# DispenGSM.net
KiCad netlist of a schematic drawn in EAGLE
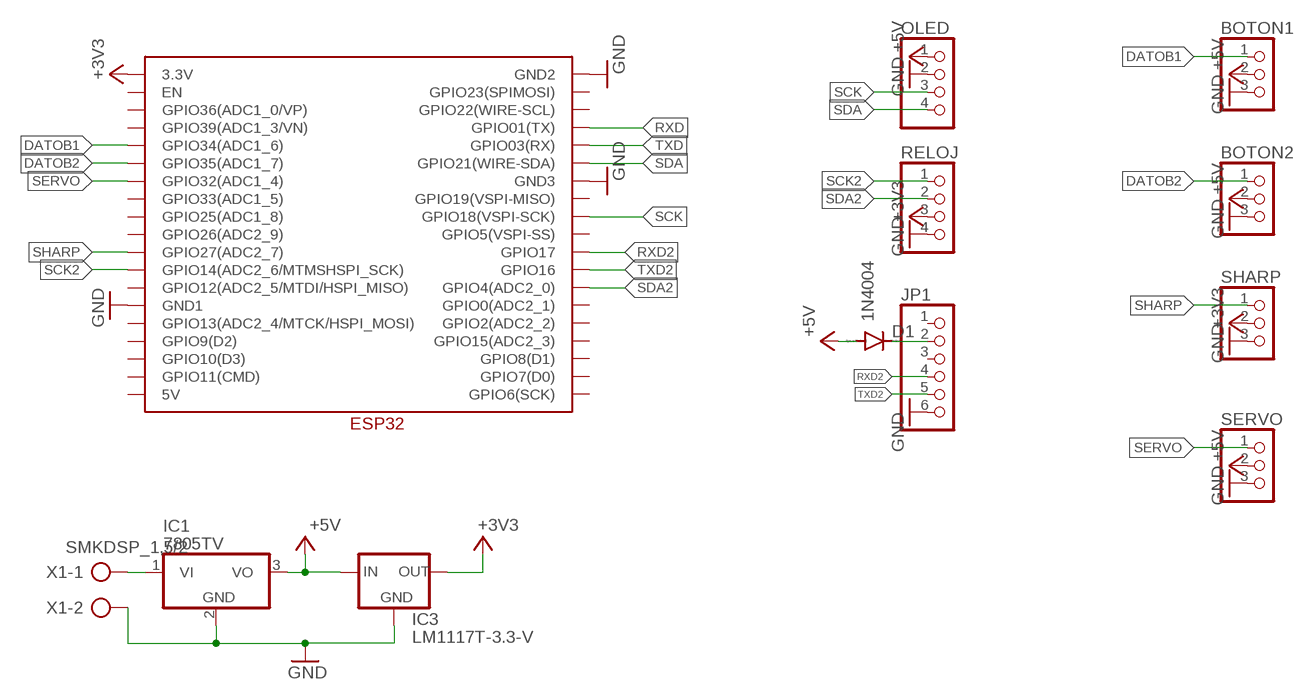
[diagram p0: schematic, sheet 1]

(export (version "E")
  (design (tool "Eeschema 10.0.6"))
  (components
    (comp (ref "BOTON1")
      (value "PINHD-1X3")
      (footprint "eagle-import:1X03")
      (libsource (lib "eagle-import") (part "PINHD-1X3"))
    )
    (comp (ref "BOTON2")
      (value "PINHD-1X3")
      (footprint "eagle-import:1X03")
      (libsource (lib "eagle-import") (part "PINHD-1X3"))
    )
    (comp (ref "D1")
      (value "1N4004")
      (footprint "eagle-import:DO41-10")
      (libsource (lib "eagle-import") (part "1N4004"))
    )
    (comp (ref "IC1")
      (value "7805TV")
      (footprint "eagle-import:TO220V")
      (libsource (lib "eagle-import") (part "78TV05"))
    )
    (comp (ref "IC3")
      (value "LM1117T-3.3-V")
      (footprint "eagle-import:TO220V")
      (libsource (lib "eagle-import") (part "LM1117T--V3.3"))
    )
    (comp (ref "JP1")
      (value "PINHD-1X6")
      (footprint "eagle-import:1X06")
      (libsource (lib "eagle-import") (part "PINHD-1X6"))
    )
    (comp (ref "OLED")
      (value "PINHD-1X4")
      (footprint "eagle-import:1X04")
      (libsource (lib "eagle-import") (part "PINHD-1X4"))
    )
    (comp (ref "RELOJ")
      (value "PINHD-1X4")
      (footprint "eagle-import:1X04")
      (libsource (lib "eagle-import") (part "PINHD-1X4"))
    )
    (comp (ref "SERVO")
      (value "PINHD-1X3")
      (footprint "eagle-import:1X03")
      (libsource (lib "eagle-import") (part "PINHD-1X3"))
    )
    (comp (ref "SHARP")
      (value "PINHD-1X3")
      (footprint "eagle-import:1X03")
      (libsource (lib "eagle-import") (part "PINHD-1X3"))
    )
    (comp (ref "U$1")
      (value "ESP32WESP32W")
      (footprint "eagle-import:ESP32W")
      (libsource (lib "eagle-import") (part "ESP32WESP32W"))
    )
    (comp (ref "X1")
      (value "SMKDSP_1,5/2")
      (footprint "eagle-import:SMKDSP_1,5_2")
      (fields (field (name "MF") "FARNELL") (field (name "MPN") "1733570"))
      (libsource (lib "eagle-import") (part "SMKDSP_1,5/2"))
    )
  )
  (nets
    (net (code "1") (name "+3V3") (class "Default")
      (node (ref "IC3") (pin "2") (pinfunction "OUT_2") (pintype "passive"))
      (node (ref "RELOJ") (pin "3") (pinfunction "3_3") (pintype "passive"))
      (node (ref "SHARP") (pin "2") (pinfunction "2_2") (pintype "passive"))
      (node (ref "U$1") (pin "3.3V") (pinfunction "3.3V_3.3V") (pintype "bidirectional"))
    )
    (net (code "2") (name "+5V") (class "Default")
      (node (ref "BOTON1") (pin "2") (pinfunction "2_2") (pintype "passive"))
      (node (ref "BOTON2") (pin "2") (pinfunction "2_2") (pintype "passive"))
      (node (ref "D1") (pin "A") (pinfunction "A_A") (pintype "passive"))
      (node (ref "IC1") (pin "3") (pinfunction "VO_3") (pintype "passive"))
      (node (ref "IC3") (pin "3") (pinfunction "IN_3") (pintype "input"))
      (node (ref "OLED") (pin "1") (pinfunction "1_1") (pintype "passive"))
      (node (ref "SERVO") (pin "2") (pinfunction "2_2") (pintype "passive"))
    )
    (net (code "3") (name "DATOB1") (class "Default")
      (node (ref "BOTON1") (pin "1") (pinfunction "1_1") (pintype "passive"))
      (node (ref "U$1") (pin "GPIO34") (pinfunction "GPIO34(ADC1_6)_GPIO34") (pintype "bidirectional"))
    )
    (net (code "4") (name "DATOB2") (class "Default")
      (node (ref "BOTON2") (pin "1") (pinfunction "1_1") (pintype "passive"))
      (node (ref "U$1") (pin "GPIO35") (pinfunction "GPIO35(ADC1_7)_GPIO35") (pintype "bidirectional"))
    )
    (net (code "5") (name "GND") (class "Default")
      (node (ref "BOTON1") (pin "3") (pinfunction "3_3") (pintype "passive"))
      (node (ref "BOTON2") (pin "3") (pinfunction "3_3") (pintype "passive"))
      (node (ref "IC1") (pin "2") (pinfunction "GND_2") (pintype "passive"))
      (node (ref "IC3") (pin "1") (pinfunction "GND_1") (pintype "input"))
      (node (ref "JP1") (pin "6") (pinfunction "6_6") (pintype "passive"))
      (node (ref "OLED") (pin "2") (pinfunction "2_2") (pintype "passive"))
      (node (ref "RELOJ") (pin "4") (pinfunction "4_4") (pintype "passive"))
      (node (ref "SERVO") (pin "3") (pinfunction "3_3") (pintype "passive"))
      (node (ref "SHARP") (pin "3") (pinfunction "3_3") (pintype "passive"))
      (node (ref "U$1") (pin "GND1") (pinfunction "GND1_GND1") (pintype "bidirectional"))
      (node (ref "U$1") (pin "GND2") (pinfunction "GND2_GND2") (pintype "bidirectional"))
      (node (ref "U$1") (pin "GND3") (pinfunction "GND3_GND3") (pintype "bidirectional"))
      (node (ref "X1") (pin "2") (pinfunction "KL_2") (pintype "passive"))
    )
    (net (code "6") (name "Net-(D1-PadC)") (class "Default")
      (node (ref "D1") (pin "C") (pinfunction "C_C") (pintype "passive"))
      (node (ref "JP1") (pin "2") (pinfunction "2_2") (pintype "passive"))
    )
    (net (code "7") (name "Net-(IC1-VI)") (class "Default")
      (node (ref "IC1") (pin "1") (pinfunction "VI_1") (pintype "input"))
      (node (ref "X1") (pin "1") (pinfunction "KL_1") (pintype "passive"))
    )
    (net (code "8") (name "RXD") (class "Default")
      (node (ref "U$1") (pin "TX") (pinfunction "GPIO01(TX)_TX") (pintype "bidirectional"))
    )
    (net (code "9") (name "RXD2") (class "Default")
      (node (ref "JP1") (pin "4") (pinfunction "4_4") (pintype "passive"))
      (node (ref "U$1") (pin "GPIO17") (pinfunction "GPIO17_GPIO17") (pintype "bidirectional"))
    )
    (net (code "10") (name "SCK") (class "Default")
      (node (ref "OLED") (pin "3") (pinfunction "3_3") (pintype "passive"))
      (node (ref "U$1") (pin "GPIO18") (pinfunction "GPIO18(VSPI-SCK)_GPIO18") (pintype "bidirectional"))
    )
    (net (code "11") (name "SCK2") (class "Default")
      (node (ref "RELOJ") (pin "1") (pinfunction "1_1") (pintype "passive"))
      (node (ref "U$1") (pin "GPIO14") (pinfunction "GPIO14(ADC2_6/MTMSHSPI_SCK)_GPIO14") (pintype "bidirectional"))
    )
    (net (code "12") (name "SDA") (class "Default")
      (node (ref "OLED") (pin "4") (pinfunction "4_4") (pintype "passive"))
      (node (ref "U$1") (pin "GPIO21") (pinfunction "GPIO21(WIRE-SDA)_GPIO21") (pintype "bidirectional"))
    )
    (net (code "13") (name "SDA2") (class "Default")
      (node (ref "RELOJ") (pin "2") (pinfunction "2_2") (pintype "passive"))
      (node (ref "U$1") (pin "GPIO4") (pinfunction "GPIO4(ADC2_0)_GPIO4") (pintype "bidirectional"))
    )
    (net (code "14") (name "SERVO") (class "Default")
      (node (ref "SERVO") (pin "1") (pinfunction "1_1") (pintype "passive"))
      (node (ref "U$1") (pin "GPIO32") (pinfunction "GPIO32(ADC1_4)_GPIO32") (pintype "bidirectional"))
    )
    (net (code "15") (name "SHARP") (class "Default")
      (node (ref "SHARP") (pin "1") (pinfunction "1_1") (pintype "passive"))
      (node (ref "U$1") (pin "GPIO27") (pinfunction "GPIO27(ADC2_7)_GPIO27") (pintype "bidirectional"))
    )
    (net (code "16") (name "TXD") (class "Default")
      (node (ref "U$1") (pin "RX") (pinfunction "GPIO03(RX)_RX") (pintype "bidirectional"))
    )
    (net (code "17") (name "TXD2") (class "Default")
      (node (ref "JP1") (pin "5") (pinfunction "5_5") (pintype "passive"))
      (node (ref "U$1") (pin "GPIO16") (pinfunction "GPIO16_GPIO16") (pintype "bidirectional"))
    )
    (net (code "18") (name "unconnected-(JP1-Pad1)") (class "Default")
      (node (ref "JP1") (pin "1") (pinfunction "1_1") (pintype "passive"))
    )
    (net (code "19") (name "unconnected-(JP1-Pad3)") (class "Default")
      (node (ref "JP1") (pin "3") (pinfunction "3_3") (pintype "passive"))
    )
    (net (code "20") (name "unconnected-(U$1-GPIO0(ADC2_1)-PadGPIO0)") (class "Default")
      (node (ref "U$1") (pin "GPIO0") (pinfunction "GPIO0(ADC2_1)_GPIO0") (pintype "bidirectional"))
    )
    (net (code "21") (name "unconnected-(U$1-GPIO2(ADC2_2)-PadGPIO2)") (class "Default")
      (node (ref "U$1") (pin "GPIO2") (pinfunction "GPIO2(ADC2_2)_GPIO2") (pintype "bidirectional"))
    )
    (net (code "22") (name "unconnected-(U$1-GPIO5(VSPI-SS)-PadGPIO5)") (class "Default")
      (node (ref "U$1") (pin "GPIO5") (pinfunction "GPIO5(VSPI-SS)_GPIO5") (pintype "bidirectional"))
    )
    (net (code "23") (name "unconnected-(U$1-GPIO6(SCK)-PadCLK)") (class "Default")
      (node (ref "U$1") (pin "CLK") (pinfunction "GPIO6(SCK)_CLK") (pintype "bidirectional"))
    )
    (net (code "24") (name "unconnected-(U$1-GPIO7(D0)-PadSDO)") (class "Default")
      (node (ref "U$1") (pin "SDO") (pinfunction "GPIO7(D0)_SDO") (pintype "bidirectional"))
    )
    (net (code "25") (name "unconnected-(U$1-GPIO8(D1)-PadSDI)") (class "Default")
      (node (ref "U$1") (pin "SDI") (pinfunction "GPIO8(D1)_SDI") (pintype "bidirectional"))
    )
    (net (code "26") (name "unconnected-(U$1-GPIO9(D2)-PadD2)") (class "Default")
      (node (ref "U$1") (pin "D2") (pinfunction "GPIO9(D2)_D2") (pintype "bidirectional"))
    )
    (net (code "27") (name "unconnected-(U$1-GPIO10(D3)-PadD3)") (class "Default")
      (node (ref "U$1") (pin "D3") (pinfunction "GPIO10(D3)_D3") (pintype "bidirectional"))
    )
    (net (code "28") (name "unconnected-(U$1-GPIO11(CMD)-PadCMD)") (class "Default")
      (node (ref "U$1") (pin "CMD") (pinfunction "GPIO11(CMD)_CMD") (pintype "bidirectional"))
    )
    (net (code "29") (name "unconnected-(U$1-GPIO12(ADC2_5{slash}MTDI{slash}HSPI_MISO)-PadGPIO12)") (class "Default")
      (node (ref "U$1") (pin "GPIO12") (pinfunction "GPIO12(ADC2_5/MTDI/HSPI_MISO)_GPIO12") (pintype "bidirectional"))
    )
    (net (code "30") (name "unconnected-(U$1-GPIO13(ADC2_4{slash}MTCK{slash}HSPI_MOSI)-PadGPIO13)") (class "Default")
      (node (ref "U$1") (pin "GPIO13") (pinfunction "GPIO13(ADC2_4/MTCK/HSPI_MOSI)_GPIO13") (pintype "bidirectional"))
    )
    (net (code "31") (name "unconnected-(U$1-GPIO15(ADC2_3)-PadGPIO15)") (class "Default")
      (node (ref "U$1") (pin "GPIO15") (pinfunction "GPIO15(ADC2_3)_GPIO15") (pintype "bidirectional"))
    )
    (net (code "32") (name "unconnected-(U$1-GPIO19(VSPI-MISO)-PadGPIO19)") (class "Default")
      (node (ref "U$1") (pin "GPIO19") (pinfunction "GPIO19(VSPI-MISO)_GPIO19") (pintype "bidirectional"))
    )
    (net (code "33") (name "unconnected-(U$1-GPIO22(WIRE-SCL)-PadGPIO22)") (class "Default")
      (node (ref "U$1") (pin "GPIO22") (pinfunction "GPIO22(WIRE-SCL)_GPIO22") (pintype "bidirectional"))
    )
    (net (code "34") (name "unconnected-(U$1-GPIO23(SPIMOSI)-PadGPIO23)") (class "Default")
      (node (ref "U$1") (pin "GPIO23") (pinfunction "GPIO23(SPIMOSI)_GPIO23") (pintype "bidirectional"))
    )
    (net (code "35") (name "unconnected-(U$1-GPIO25(ADC1_8)-PadGPIO25)") (class "Default")
      (node (ref "U$1") (pin "GPIO25") (pinfunction "GPIO25(ADC1_8)_GPIO25") (pintype "bidirectional"))
    )
    (net (code "36") (name "unconnected-(U$1-GPIO26(ADC2_9)-PadGPIO26)") (class "Default")
      (node (ref "U$1") (pin "GPIO26") (pinfunction "GPIO26(ADC2_9)_GPIO26") (pintype "bidirectional"))
    )
    (net (code "37") (name "unconnected-(U$1-GPIO33(ADC1_5)-PadGPIO33)") (class "Default")
      (node (ref "U$1") (pin "GPIO33") (pinfunction "GPIO33(ADC1_5)_GPIO33") (pintype "bidirectional"))
    )
    (net (code "38") (name "unconnected-(U$1-GPIO36(ADC1_0{slash}VP)-PadVP)") (class "Default")
      (node (ref "U$1") (pin "VP") (pinfunction "GPIO36(ADC1_0/VP)_VP") (pintype "bidirectional"))
    )
    (net (code "39") (name "unconnected-(U$1-GPIO39(ADC1_3{slash}VN)-PadVN)") (class "Default")
      (node (ref "U$1") (pin "VN") (pinfunction "GPIO39(ADC1_3/VN)_VN") (pintype "bidirectional"))
    )
    (net (code "40") (name "unconnected-(U$1-Pad5V)") (class "Default")
      (node (ref "U$1") (pin "5V") (pinfunction "5V_5V") (pintype "bidirectional"))
    )
    (net (code "41") (name "unconnected-(U$1-PadEN)") (class "Default")
      (node (ref "U$1") (pin "EN") (pinfunction "EN_EN") (pintype "bidirectional"))
    )
  )
)
